# Lumos_v_0_2.net
KiCad netlist of a schematic drawn in Altium Designer
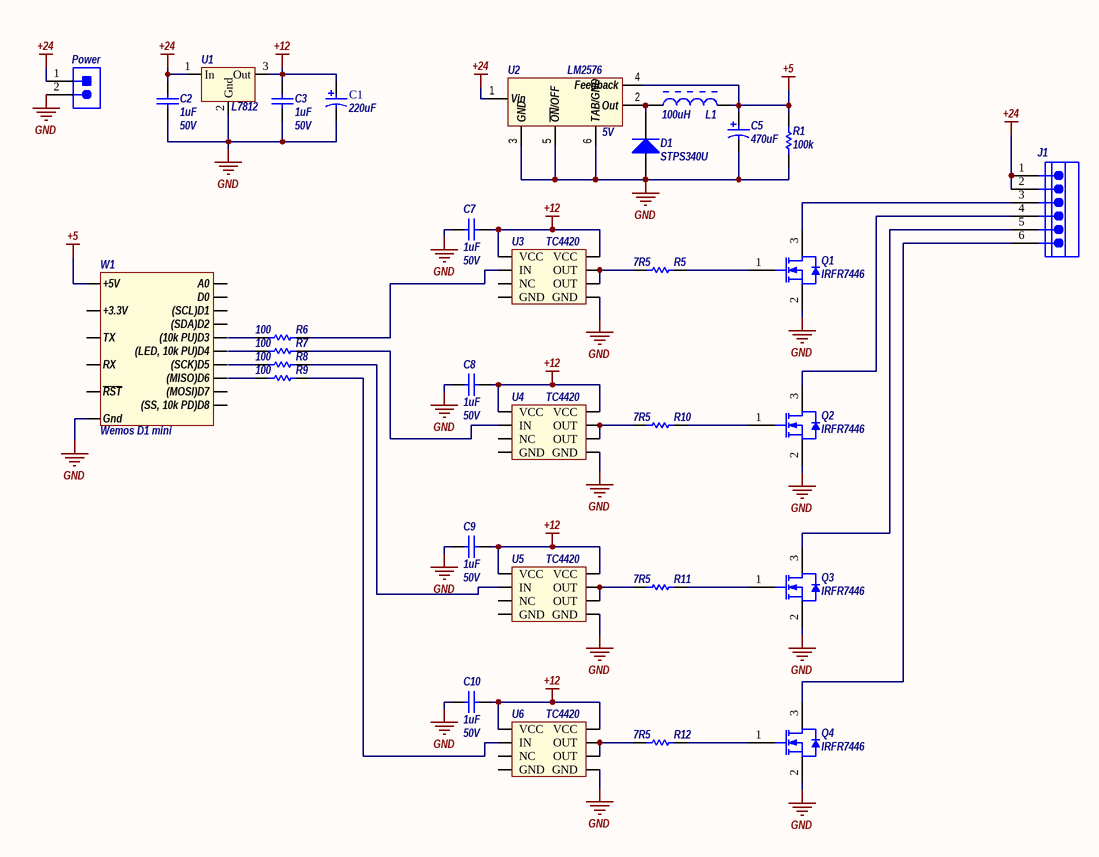
[diagram p0: Lumos_v.0.2.SchDoc]

(export (version "E")
  (design (tool "Eeschema 10.0.6"))
  (components
    (comp (ref "C1")
      (value "220uF")
      (footprint "ECAP_Radial_8x11")
      (fields (field (name "VOLTAGE") "25V"))
      (libsource (lib "ECAP_Radial") (part "ECAP_Radial_8x11"))
    )
    (comp (ref "C2")
      (value "1uF")
      (footprint "CAPC0805")
      (fields (field (name "VOLTAGE") "50V"))
      (libsource (lib "Misc") (part "CAP_SMD_ceramic"))
    )
    (comp (ref "C3")
      (value "1uF")
      (footprint "CAPC0805")
      (fields (field (name "VOLTAGE") "50V"))
      (libsource (lib "Misc") (part "CAP_SMD_ceramic"))
    )
    (comp (ref "C5")
      (value "470uF")
      (footprint "ECAP_Radial_8x11")
      (libsource (lib "ECAP_Radial") (part "ECAP_Radial_8x11"))
    )
    (comp (ref "C7")
      (value "1uF")
      (footprint "CAPC0805")
      (fields (field (name "VOLTAGE") "50V"))
      (libsource (lib "Misc") (part "CAP_SMD_ceramic"))
    )
    (comp (ref "C8")
      (value "1uF")
      (footprint "CAPC0805")
      (fields (field (name "VOLTAGE") "50V"))
      (libsource (lib "Misc") (part "CAP_SMD_ceramic"))
    )
    (comp (ref "C9")
      (value "1uF")
      (footprint "CAPC0805")
      (fields (field (name "VOLTAGE") "50V"))
      (libsource (lib "Misc") (part "CAP_SMD_ceramic"))
    )
    (comp (ref "C10")
      (value "1uF")
      (footprint "CAPC0805")
      (fields (field (name "VOLTAGE") "50V"))
      (libsource (lib "Misc") (part "CAP_SMD_ceramic"))
    )
    (comp (ref "D1") (value "STPS340U") (footprint "SMB") (libsource (lib "Misc") (part "Diode")))
    (comp (ref "J1")
      (value "KMRJ103-5.0/508 6WAYS")
      (footprint "KONV-KMRJ103-5-508-6_V")
      (description "Socket, Screw Terminal Block, 6 Way, 5.0mm Pitch, 45 Degree Angle, Through-hole")
      (fields (field (name "MANUFACTURER") "Konvee Electronic"))
      (libsource (lib "Altium Content Vault") (part "KONV-KMRJ103-5-508-6"))
    )
    (comp (ref "L1") (value "100uH") (footprint "RLB1314-101KL") (libsource (lib "Misc") (part "Inductor")))
    (comp (ref "Power")
      (value "SCREW-5.0/5.08 2WAYS")
      (footprint "SCREW-5.0-2WAYS_V")
      (description "Socket, Screw Terminal Block, 2 Way, 5.0 mm Pitch, 90 Degree Angle, Through-Hole")
      (fields (field (name "MANUFACTURER") "No Vendor"))
      (libsource (lib "Altium Content Vault") (part "SCREW-2WAYS"))
    )
    (comp (ref "Q1") (value "IRFR7446") (footprint "D-PAK") (libsource (lib "Misc") (part "MOSFET-N")))
    (comp (ref "Q2") (value "IRFR7446") (footprint "D-PAK") (libsource (lib "Misc") (part "MOSFET-N")))
    (comp (ref "Q3") (value "IRFR7446") (footprint "D-PAK") (libsource (lib "Misc") (part "MOSFET-N")))
    (comp (ref "Q4") (value "IRFR7446") (footprint "D-PAK") (libsource (lib "Misc") (part "MOSFET-N")))
    (comp (ref "R1") (value "100k") (footprint "RES1206") (libsource (lib "Misc") (part "RES_SMD")))
    (comp (ref "R5") (value "7R5") (footprint "RES1206") (libsource (lib "Misc") (part "RES_SMD")))
    (comp (ref "R6") (value "100") (footprint "RES0603") (libsource (lib "Misc") (part "RES_SMD")))
    (comp (ref "R7") (value "100") (footprint "RES0603") (libsource (lib "Misc") (part "RES_SMD")))
    (comp (ref "R8") (value "100") (footprint "RES0603") (libsource (lib "Misc") (part "RES_SMD")))
    (comp (ref "R9") (value "100") (footprint "RES0603") (libsource (lib "Misc") (part "RES_SMD")))
    (comp (ref "R10") (value "7R5") (footprint "RES1206") (libsource (lib "Misc") (part "RES_SMD")))
    (comp (ref "R11") (value "7R5") (footprint "RES1206") (libsource (lib "Misc") (part "RES_SMD")))
    (comp (ref "R12") (value "7R5") (footprint "RES1206") (libsource (lib "Misc") (part "RES_SMD")))
    (comp (ref "U1") (value "L7812") (footprint "D2PAK-2") (libsource (lib "IC") (part "L78xx")))
    (comp (ref "U2")
      (value "5V")
      (footprint "TO-263-5")
      (fields (field (name "MODEL") "LM2576"))
      (libsource (lib "IC") (part "LM2576"))
    )
    (comp (ref "U3") (value "TC4420") (footprint "SO-8") (libsource (lib "IC") (part "TC4420")))
    (comp (ref "U4") (value "TC4420") (footprint "SO-8") (libsource (lib "IC") (part "TC4420")))
    (comp (ref "U5") (value "TC4420") (footprint "SO-8") (libsource (lib "IC") (part "TC4420")))
    (comp (ref "U6") (value "TC4420") (footprint "SO-8") (libsource (lib "IC") (part "TC4420")))
    (comp (ref "W1")
      (value "Wemos D1 mini")
      (footprint "Wemos D1 mini")
      (libsource (lib "Misc") (part "Wemos D1 mini"))
    )
  )
  (nets
    (net (code "1") (name "+5") (class "Default")
      (node (ref "C5") (pin "1") (pinfunction "1_1") (pintype "passive"))
      (node (ref "L1") (pin "2") (pinfunction "2_2") (pintype "passive"))
      (node (ref "R1") (pin "2") (pinfunction "2_2") (pintype "passive"))
      (node (ref "U2") (pin "4") (pinfunction "Feedback_4") (pintype "passive"))
      (node (ref "W1") (pin "+5V") (pinfunction "+5V_+5V") (pintype "passive"))
    )
    (net (code "2") (name "+12") (class "Default")
      (node (ref "C1") (pin "1") (pinfunction "1_1") (pintype "passive"))
      (node (ref "C10") (pin "2") (pinfunction "2_2") (pintype "passive"))
      (node (ref "C3") (pin "2") (pinfunction "2_2") (pintype "passive"))
      (node (ref "C7") (pin "2") (pinfunction "2_2") (pintype "passive"))
      (node (ref "C8") (pin "2") (pinfunction "2_2") (pintype "passive"))
      (node (ref "C9") (pin "2") (pinfunction "2_2") (pintype "passive"))
      (node (ref "U1") (pin "3") (pinfunction "Out_3") (pintype "passive"))
      (node (ref "U3") (pin "1") (pinfunction "VCC_1") (pintype "passive"))
      (node (ref "U3") (pin "8") (pinfunction "VCC_8") (pintype "passive"))
      (node (ref "U4") (pin "1") (pinfunction "VCC_1") (pintype "passive"))
      (node (ref "U4") (pin "8") (pinfunction "VCC_8") (pintype "passive"))
      (node (ref "U5") (pin "1") (pinfunction "VCC_1") (pintype "passive"))
      (node (ref "U5") (pin "8") (pinfunction "VCC_8") (pintype "passive"))
      (node (ref "U6") (pin "1") (pinfunction "VCC_1") (pintype "passive"))
      (node (ref "U6") (pin "8") (pinfunction "VCC_8") (pintype "passive"))
    )
    (net (code "3") (name "+24") (class "Default")
      (node (ref "C2") (pin "2") (pinfunction "2_2") (pintype "passive"))
      (node (ref "J1") (pin "1") (pinfunction "1_1") (pintype "passive"))
      (node (ref "J1") (pin "2") (pinfunction "2_2") (pintype "passive"))
      (node (ref "Power") (pin "1") (pinfunction "1_1") (pintype "passive"))
      (node (ref "U1") (pin "1") (pinfunction "In_1") (pintype "passive"))
      (node (ref "U2") (pin "1") (pinfunction "Vin_1") (pintype "passive"))
    )
    (net (code "4") (name "GND") (class "Default")
      (node (ref "C1") (pin "2") (pinfunction "2_2") (pintype "passive"))
      (node (ref "C10") (pin "1") (pinfunction "1_1") (pintype "passive"))
      (node (ref "C2") (pin "1") (pinfunction "1_1") (pintype "passive"))
      (node (ref "C3") (pin "1") (pinfunction "1_1") (pintype "passive"))
      (node (ref "C5") (pin "2") (pinfunction "2_2") (pintype "passive"))
      (node (ref "C7") (pin "1") (pinfunction "1_1") (pintype "passive"))
      (node (ref "C8") (pin "1") (pinfunction "1_1") (pintype "passive"))
      (node (ref "C9") (pin "1") (pinfunction "1_1") (pintype "passive"))
      (node (ref "D1") (pin "1") (pinfunction "A_1") (pintype "passive"))
      (node (ref "Power") (pin "2") (pinfunction "2_2") (pintype "passive"))
      (node (ref "Q1") (pin "2") (pinfunction "S_2") (pintype "passive"))
      (node (ref "Q2") (pin "2") (pinfunction "S_2") (pintype "passive"))
      (node (ref "Q3") (pin "2") (pinfunction "S_2") (pintype "passive"))
      (node (ref "Q4") (pin "2") (pinfunction "S_2") (pintype "passive"))
      (node (ref "R1") (pin "1") (pinfunction "1_1") (pintype "passive"))
      (node (ref "U1") (pin "2") (pinfunction "Gnd_2") (pintype "passive"))
      (node (ref "U2") (pin "3") (pinfunction "GND_3") (pintype "passive"))
      (node (ref "U2") (pin "5") (pinfunction "~{ON}/OFF_5") (pintype "passive"))
      (node (ref "U2") (pin "6") (pinfunction "TAB/GND_6") (pintype "passive"))
      (node (ref "U3") (pin "5") (pinfunction "GND_5") (pintype "passive"))
      (node (ref "U4") (pin "5") (pinfunction "GND_5") (pintype "passive"))
      (node (ref "U5") (pin "5") (pinfunction "GND_5") (pintype "passive"))
      (node (ref "U6") (pin "5") (pinfunction "GND_5") (pintype "passive"))
      (node (ref "W1") (pin "Gnd") (pinfunction "Gnd_Gnd") (pintype "passive"))
    )
    (net (code "5") (name "Net-(D1-K)") (class "Default")
      (node (ref "D1") (pin "2") (pinfunction "K_2") (pintype "passive"))
      (node (ref "L1") (pin "1") (pinfunction "1_1") (pintype "passive"))
      (node (ref "U2") (pin "2") (pinfunction "Out_2") (pintype "passive"))
    )
    (net (code "6") (name "Net-(Q1-D)") (class "Default")
      (node (ref "J1") (pin "3") (pinfunction "3_3") (pintype "passive"))
      (node (ref "Q1") (pin "3") (pinfunction "D_3") (pintype "passive"))
    )
    (net (code "7") (name "Net-(Q1-G)") (class "Default")
      (node (ref "Q1") (pin "1") (pinfunction "G_1") (pintype "passive"))
      (node (ref "R5") (pin "2") (pinfunction "2_2") (pintype "passive"))
    )
    (net (code "8") (name "Net-(Q2-D)") (class "Default")
      (node (ref "J1") (pin "4") (pinfunction "4_4") (pintype "passive"))
      (node (ref "Q2") (pin "3") (pinfunction "D_3") (pintype "passive"))
    )
    (net (code "9") (name "Net-(Q2-G)") (class "Default")
      (node (ref "Q2") (pin "1") (pinfunction "G_1") (pintype "passive"))
      (node (ref "R10") (pin "2") (pinfunction "2_2") (pintype "passive"))
    )
    (net (code "10") (name "Net-(Q3-D)") (class "Default")
      (node (ref "J1") (pin "5") (pinfunction "5_5") (pintype "passive"))
      (node (ref "Q3") (pin "3") (pinfunction "D_3") (pintype "passive"))
    )
    (net (code "11") (name "Net-(Q3-G)") (class "Default")
      (node (ref "Q3") (pin "1") (pinfunction "G_1") (pintype "passive"))
      (node (ref "R11") (pin "2") (pinfunction "2_2") (pintype "passive"))
    )
    (net (code "12") (name "Net-(Q4-D)") (class "Default")
      (node (ref "J1") (pin "6") (pinfunction "6_6") (pintype "passive"))
      (node (ref "Q4") (pin "3") (pinfunction "D_3") (pintype "passive"))
    )
    (net (code "13") (name "Net-(Q4-G)") (class "Default")
      (node (ref "Q4") (pin "1") (pinfunction "G_1") (pintype "passive"))
      (node (ref "R12") (pin "2") (pinfunction "2_2") (pintype "passive"))
    )
    (net (code "14") (name "Net-(R5-Pad1)") (class "Default")
      (node (ref "R5") (pin "1") (pinfunction "1_1") (pintype "passive"))
      (node (ref "U3") (pin "6") (pinfunction "OUT_6") (pintype "passive"))
      (node (ref "U3") (pin "7") (pinfunction "OUT_7") (pintype "passive"))
    )
    (net (code "15") (name "Net-(R10-Pad1)") (class "Default")
      (node (ref "R10") (pin "1") (pinfunction "1_1") (pintype "passive"))
      (node (ref "U4") (pin "6") (pinfunction "OUT_6") (pintype "passive"))
      (node (ref "U4") (pin "7") (pinfunction "OUT_7") (pintype "passive"))
    )
    (net (code "16") (name "Net-(R11-Pad1)") (class "Default")
      (node (ref "R11") (pin "1") (pinfunction "1_1") (pintype "passive"))
      (node (ref "U5") (pin "6") (pinfunction "OUT_6") (pintype "passive"))
      (node (ref "U5") (pin "7") (pinfunction "OUT_7") (pintype "passive"))
    )
    (net (code "17") (name "Net-(R12-Pad1)") (class "Default")
      (node (ref "R12") (pin "1") (pinfunction "1_1") (pintype "passive"))
      (node (ref "U6") (pin "6") (pinfunction "OUT_6") (pintype "passive"))
      (node (ref "U6") (pin "7") (pinfunction "OUT_7") (pintype "passive"))
    )
    (net (code "18") (name "Net-(U3-IN)") (class "Default")
      (node (ref "R6") (pin "2") (pinfunction "2_2") (pintype "passive"))
      (node (ref "U3") (pin "2") (pinfunction "IN_2") (pintype "passive"))
    )
    (net (code "19") (name "Net-(U4-IN)") (class "Default")
      (node (ref "R7") (pin "2") (pinfunction "2_2") (pintype "passive"))
      (node (ref "U4") (pin "2") (pinfunction "IN_2") (pintype "passive"))
    )
    (net (code "20") (name "Net-(U5-IN)") (class "Default")
      (node (ref "R8") (pin "2") (pinfunction "2_2") (pintype "passive"))
      (node (ref "U5") (pin "2") (pinfunction "IN_2") (pintype "passive"))
    )
    (net (code "21") (name "Net-(U6-IN)") (class "Default")
      (node (ref "R9") (pin "2") (pinfunction "2_2") (pintype "passive"))
      (node (ref "U6") (pin "2") (pinfunction "IN_2") (pintype "passive"))
    )
    (net (code "22") (name "unconnected-(R6-Pad1)") (class "Default")
      (node (ref "R6") (pin "1") (pinfunction "1_1") (pintype "passive"))
    )
    (net (code "23") (name "unconnected-(R7-Pad1)") (class "Default")
      (node (ref "R7") (pin "1") (pinfunction "1_1") (pintype "passive"))
    )
    (net (code "24") (name "unconnected-(R8-Pad1)") (class "Default")
      (node (ref "R8") (pin "1") (pinfunction "1_1") (pintype "passive"))
    )
    (net (code "25") (name "unconnected-(R9-Pad1)") (class "Default")
      (node (ref "R9") (pin "1") (pinfunction "1_1") (pintype "passive"))
    )
    (net (code "26") (name "unconnected-(U3-GND-Pad4)") (class "Default")
      (node (ref "U3") (pin "4") (pinfunction "GND_4") (pintype "passive"))
    )
    (net (code "27") (name "unconnected-(U3-NC-Pad3)") (class "Default")
      (node (ref "U3") (pin "3") (pinfunction "NC_3") (pintype "passive"))
    )
    (net (code "28") (name "unconnected-(U4-GND-Pad4)") (class "Default")
      (node (ref "U4") (pin "4") (pinfunction "GND_4") (pintype "passive"))
    )
    (net (code "29") (name "unconnected-(U4-NC-Pad3)") (class "Default")
      (node (ref "U4") (pin "3") (pinfunction "NC_3") (pintype "passive"))
    )
    (net (code "30") (name "unconnected-(U5-GND-Pad4)") (class "Default")
      (node (ref "U5") (pin "4") (pinfunction "GND_4") (pintype "passive"))
    )
    (net (code "31") (name "unconnected-(U5-NC-Pad3)") (class "Default")
      (node (ref "U5") (pin "3") (pinfunction "NC_3") (pintype "passive"))
    )
    (net (code "32") (name "unconnected-(U6-GND-Pad4)") (class "Default")
      (node (ref "U6") (pin "4") (pinfunction "GND_4") (pintype "passive"))
    )
    (net (code "33") (name "unconnected-(U6-NC-Pad3)") (class "Default")
      (node (ref "U6") (pin "3") (pinfunction "NC_3") (pintype "passive"))
    )
    (net (code "34") (name "unconnected-(W1-(10k_PU)D3-PadD3)") (class "Default")
      (node (ref "W1") (pin "D3") (pinfunction "(10k_PU)D3_D3") (pintype "passive"))
    )
    (net (code "35") (name "unconnected-(W1-(LED,_10k_PU)D4-PadD4)") (class "Default")
      (node (ref "W1") (pin "D4") (pinfunction "(LED,_10k_PU)D4_D4") (pintype "passive"))
    )
    (net (code "36") (name "unconnected-(W1-(MISO)D6-PadD6)") (class "Default")
      (node (ref "W1") (pin "D6") (pinfunction "(MISO)D6_D6") (pintype "passive"))
    )
    (net (code "37") (name "unconnected-(W1-(MOSI)D7-PadD7)") (class "Default")
      (node (ref "W1") (pin "D7") (pinfunction "(MOSI)D7_D7") (pintype "passive"))
    )
    (net (code "38") (name "unconnected-(W1-(SCK)D5-PadD5)") (class "Default")
      (node (ref "W1") (pin "D5") (pinfunction "(SCK)D5_D5") (pintype "passive"))
    )
    (net (code "39") (name "unconnected-(W1-(SCL)D1-PadD1)") (class "Default")
      (node (ref "W1") (pin "D1") (pinfunction "(SCL)D1_D1") (pintype "passive"))
    )
    (net (code "40") (name "unconnected-(W1-(SDA)D2-PadD2)") (class "Default")
      (node (ref "W1") (pin "D2") (pinfunction "(SDA)D2_D2") (pintype "passive"))
    )
    (net (code "41") (name "unconnected-(W1-(SS,_10k_PD)D8-PadD8)") (class "Default")
      (node (ref "W1") (pin "D8") (pinfunction "(SS,_10k_PD)D8_D8") (pintype "passive"))
    )
    (net (code "42") (name "unconnected-(W1-Pad+3.3V)") (class "Default")
      (node (ref "W1") (pin "+3.3V") (pinfunction "+3.3V_+3.3V") (pintype "passive"))
    )
    (net (code "43") (name "unconnected-(W1-PadA0)") (class "Default")
      (node (ref "W1") (pin "A0") (pinfunction "A0_A0") (pintype "passive"))
    )
    (net (code "44") (name "unconnected-(W1-PadD0)") (class "Default")
      (node (ref "W1") (pin "D0") (pinfunction "D0_D0") (pintype "passive"))
    )
    (net (code "45") (name "unconnected-(W1-PadRX)") (class "Default")
      (node (ref "W1") (pin "RX") (pinfunction "RX_RX") (pintype "passive"))
    )
    (net (code "46") (name "unconnected-(W1-PadTX)") (class "Default")
      (node (ref "W1") (pin "TX") (pinfunction "TX_TX") (pintype "passive"))
    )
    (net (code "47") (name "unconnected-(W1-~{RST}-PadRST)") (class "Default")
      (node (ref "W1") (pin "RST") (pinfunction "~{RST}_RST") (pintype "passive"))
    )
  )
)
